# ProProject_ESP32-S3__2023-11-30.net
KiCad netlist of a schematic drawn in EasyEDA Pro
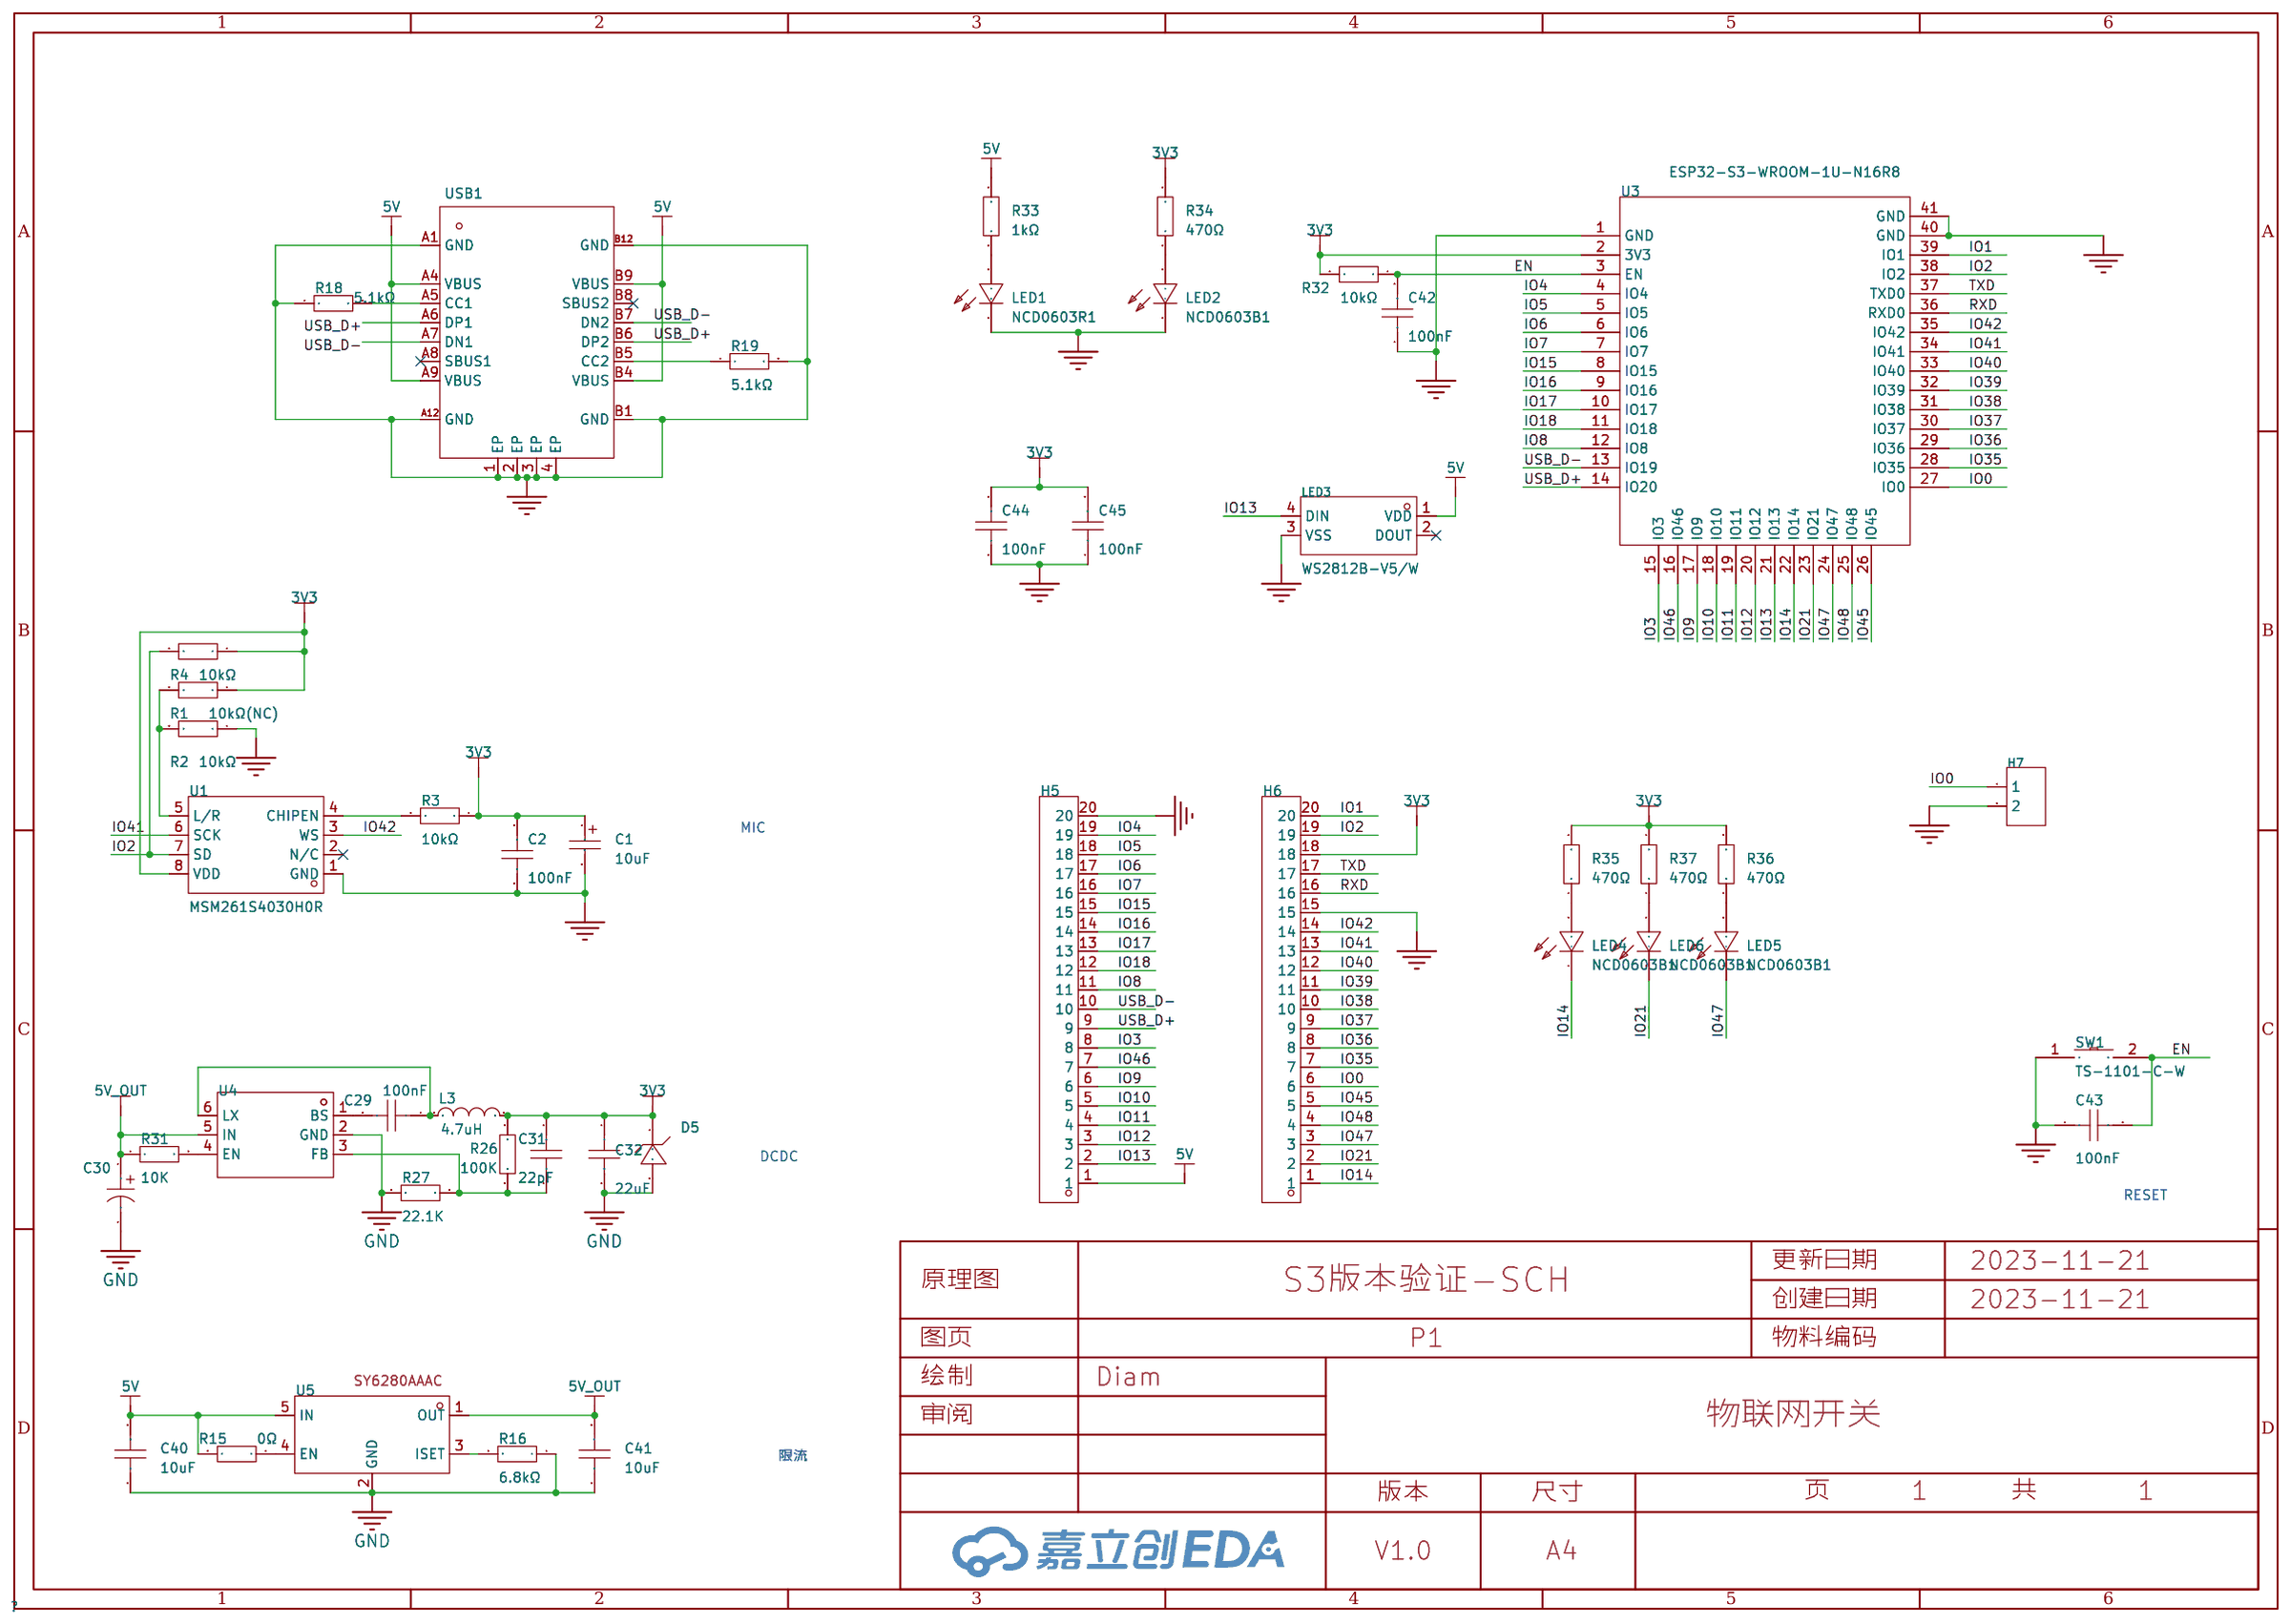
[diagram p0: schematic sheet]

(export (version "E")
  (design (tool "Eeschema 10.0.6"))
  (components
    (comp (ref "C1")
      (value "10uF")
      (footprint "easyedapro:CASE-A_3216")
      (description "容值:10uF;精度:±10%;额定电压:10V;等效串联电阻:3Ω@100kHz;")
      (fields (field (name "Manufacturer Part") "TAJA106K010RNJ") (field (name "Manufacturer") "Kyocera AVX"))
      (libsource (lib "easyedapro") (part "TAJA106K010RNJ"))
    )
    (comp (ref "C2")
      (value "100nF")
      (footprint "easyedapro:C0402")
      (description "容值:100nF;精度:±10%;额定电压:16V;材质(温度系数):X7R;")
      (fields
        (field (name "Manufacturer Part") "GRM155R71C104KA88D")
        (field (name "Manufacturer") "muRata(村田)")
      )
      (libsource (lib "easyedapro") (part "GRM155R71C104KA88D"))
    )
    (comp (ref "C29")
      (value "100nF")
      (footprint "easyedapro:C0603")
      (description "容值:100nF;精度:±10%;额定电压:50V;温度系数:X7R;")
      (libsource (lib "easyedapro") (part "C1210X7R475K630NT"))
    )
    (comp (ref "C30")
      (value "4.7uF")
      (footprint "easyedapro:CAP-SMD_L3.2-W1.6-FD")
      (libsource (lib "easyedapro") (part "YH-475P/T-贴片钽电容"))
    )
    (comp (ref "C31")
      (value "22pF")
      (footprint "easyedapro:C0603")
      (description "容值:100nF;精度:±10%;额定电压:50V;温度系数:X7R;")
      (libsource (lib "easyedapro") (part "C1210X7R475K630NT"))
    )
    (comp (ref "C32")
      (value "22uF")
      (footprint "easyedapro:C0603")
      (description "容值:100nF;精度:±10%;额定电压:50V;温度系数:X7R;")
      (libsource (lib "easyedapro") (part "C1210X7R475K630NT"))
    )
    (comp (ref "C40")
      (value "10uF")
      (footprint "easyedapro:C0603")
      (description "容值:10uF;精度:±20%;额定电压:25V;材质(温度系数):X5R;")
      (fields
        (field (name "Manufacturer Part") "CL10A106MA8NRNC")
        (field (name "Manufacturer") "SAMSUNG(三星)")
      )
      (libsource (lib "easyedapro") (part "CL10A106MA8NRNC"))
    )
    (comp (ref "C41")
      (value "10uF")
      (footprint "easyedapro:C0603")
      (description "容值:10uF;精度:±20%;额定电压:25V;材质(温度系数):X5R;")
      (fields
        (field (name "Manufacturer Part") "CL10A106MA8NRNC")
        (field (name "Manufacturer") "SAMSUNG(三星)")
      )
      (libsource (lib "easyedapro") (part "CL10A106MA8NRNC"))
    )
    (comp (ref "C42")
      (value "100nF")
      (footprint "easyedapro:C0402")
      (description "容值:100nF;精度:±10%;额定电压:16V;材质(温度系数):X7R;")
      (fields
        (field (name "Manufacturer Part") "GRM155R71C104KA88D")
        (field (name "Manufacturer") "muRata(村田)")
      )
      (libsource (lib "easyedapro") (part "GRM155R71C104KA88D"))
    )
    (comp (ref "C43")
      (value "100nF")
      (footprint "easyedapro:C0402")
      (description "容值:100nF;精度:±10%;额定电压:16V;材质(温度系数):X7R;")
      (fields
        (field (name "Manufacturer Part") "GRM155R71C104KA88D")
        (field (name "Manufacturer") "muRata(村田)")
      )
      (libsource (lib "easyedapro") (part "GRM155R71C104KA88D"))
    )
    (comp (ref "C44")
      (value "100nF")
      (footprint "easyedapro:C0402")
      (description "容值:100nF;精度:±10%;额定电压:16V;材质(温度系数):X7R;")
      (fields
        (field (name "Manufacturer Part") "GRM155R71C104KA88D")
        (field (name "Manufacturer") "muRata(村田)")
      )
      (libsource (lib "easyedapro") (part "GRM155R71C104KA88D"))
    )
    (comp (ref "C45")
      (value "100nF")
      (footprint "easyedapro:C0402")
      (description "容值:100nF;精度:±10%;额定电压:16V;材质(温度系数):X7R;")
      (fields
        (field (name "Manufacturer Part") "GRM155R71C104KA88D")
        (field (name "Manufacturer") "muRata(村田)")
      )
      (libsource (lib "easyedapro") (part "GRM155R71C104KA88D"))
    )
    (comp (ref "D5")
      (value "BZT52B3V3")
      (footprint "easyedapro:SOD-123_L2.7-W1.6-LS3.7-RD")
      (description "二极管配置:独立式;稳压值(标称值):3.3V;稳压值(范围):3.23V~3.37V;精度:-;功率:500mW;反向电流(Ir):5A@1V;阻抗(Zzt):95Ω;")
      (fields (field (name "Manufacturer") "AnBon(台湾安邦)"))
      (libsource (lib "easyedapro") (part "BZT52B3V3_C541632"))
    )
    (comp (ref "H5")
      (value "~")
      (footprint "easyedapro:HDR-TH_20P-P2.54-V-M-1")
      (libsource (lib "easyedapro") (part "HDR_2.54-1x20P"))
    )
    (comp (ref "H6")
      (value "~")
      (footprint "easyedapro:HDR-TH_20P-P2.54-V-M-1")
      (libsource (lib "easyedapro") (part "HDR_2.54-1x20P"))
    )
    (comp (ref "H7")
      (value "~")
      (footprint "easyedapro:HDR-TH_2P-P2.54-V-F")
      (libsource (lib "easyedapro") (part "Header-Female-2.54_1x2"))
    )
    (comp (ref "L3")
      (value "4.7uH")
      (footprint "easyedapro:IND-SMD_L4.5-W4.0-1")
      (description "电感值:4.7uH;精度:±20%;额定电流:2.2A;饱和电流(Isat):3.5A;直流电阻(DCR):98mΩ;")
      (fields (field (name "Manufacturer Part") "MCS0420-4R7MPN2") (field (name "Manufacturer") "PSA(信昌电陶)"))
      (libsource (lib "easyedapro") (part "MCS0420-4R7MPN2"))
    )
    (comp (ref "LED1")
      (value "NCD0603R1")
      (footprint "easyedapro:LED0603-RD_RED")
      (description "发光颜色:红色;功率:65mW;透镜颜色:无色透明;主波长:615nm~630nm;发光强度:80mcd~220mcd;发光角度:130°;工作温度:-30°C~+85°C;")
      (fields (field (name "Manufacturer") "国星光电"))
      (libsource (lib "easyedapro") (part "FC-DA1608HRK-620D"))
    )
    (comp (ref "LED2")
      (value "NCD0603B1")
      (footprint "easyedapro:LED0603-RD")
      (description "发光颜色:蓝色;功率:72mW;透镜颜色:无色透明;主波长:463nm~475nm;发光强度:80mcd~220mcd;发光角度:130°;工作温度:-30°C~+85°C;")
      (fields (field (name "Manufacturer") "国星光电"))
      (libsource (lib "easyedapro") (part "FC-DA1608BK-470H10"))
    )
    (comp (ref "LED3")
      (value "WS2812B-V5/W")
      (footprint "easyedapro:LED-SMD_4P-L5.0-W5.0-TL-1")
      (description "无需外围元器件，有反接保护和过压保护，游乐设备，消费类电子，电竞领域，电脑周边及设备")
      (fields (field (name "Manufacturer") "worldsemi"))
      (libsource (lib "easyedapro") (part "WS2812B-V5/W"))
    )
    (comp (ref "LED4")
      (value "NCD0603B1")
      (footprint "easyedapro:LED0603-RD")
      (description "发光颜色:蓝色;功率:72mW;透镜颜色:无色透明;主波长:463nm~475nm;发光强度:80mcd~220mcd;发光角度:130°;工作温度:-30°C~+85°C;")
      (fields (field (name "Manufacturer") "国星光电"))
      (libsource (lib "easyedapro") (part "FC-DA1608BK-470H10"))
    )
    (comp (ref "LED5")
      (value "NCD0603B1")
      (footprint "easyedapro:LED0603-RD")
      (description "发光颜色:蓝色;功率:72mW;透镜颜色:无色透明;主波长:463nm~475nm;发光强度:80mcd~220mcd;发光角度:130°;工作温度:-30°C~+85°C;")
      (fields (field (name "Manufacturer") "国星光电"))
      (libsource (lib "easyedapro") (part "FC-DA1608BK-470H10"))
    )
    (comp (ref "LED6")
      (value "NCD0603B1")
      (footprint "easyedapro:LED0603-RD")
      (description "发光颜色:蓝色;功率:72mW;透镜颜色:无色透明;主波长:463nm~475nm;发光强度:80mcd~220mcd;发光角度:130°;工作温度:-30°C~+85°C;")
      (fields (field (name "Manufacturer") "国星光电"))
      (libsource (lib "easyedapro") (part "FC-DA1608BK-470H10"))
    )
    (comp (ref "R1")
      (value "10kΩ(NC)")
      (footprint "easyedapro:R0402")
      (description "电阻类型:厚膜电阻;阻值:10kΩ;精度:±1%;功率:62.5mW;")
      (fields (field (name "Manufacturer Part") "RC0402FR-0710KL") (field (name "Manufacturer") "YAGEO(国巨)"))
      (libsource (lib "easyedapro") (part "RC0402FR-0710KL"))
    )
    (comp (ref "R2")
      (value "10kΩ")
      (footprint "easyedapro:R0402")
      (description "电阻类型:厚膜电阻;阻值:10kΩ;精度:±1%;功率:62.5mW;")
      (fields (field (name "Manufacturer Part") "RC0402FR-0710KL") (field (name "Manufacturer") "YAGEO(国巨)"))
      (libsource (lib "easyedapro") (part "RC0402FR-0710KL"))
    )
    (comp (ref "R3")
      (value "10kΩ")
      (footprint "easyedapro:R0402")
      (description "电阻类型:厚膜电阻;阻值:10kΩ;精度:±1%;功率:62.5mW;")
      (fields (field (name "Manufacturer Part") "RC0402FR-0710KL") (field (name "Manufacturer") "YAGEO(国巨)"))
      (libsource (lib "easyedapro") (part "RC0402FR-0710KL"))
    )
    (comp (ref "R4")
      (value "10kΩ")
      (footprint "easyedapro:R0402")
      (description "电阻类型:厚膜电阻;阻值:10kΩ;精度:±1%;功率:62.5mW;")
      (fields (field (name "Manufacturer Part") "RC0402FR-0710KL") (field (name "Manufacturer") "YAGEO(国巨)"))
      (libsource (lib "easyedapro") (part "RC0402FR-0710KL"))
    )
    (comp (ref "R15")
      (value "0Ω")
      (footprint "easyedapro:R0402")
      (description "电阻类型:厚膜电阻;阻值:0Ω;精度:±5%;功率:62.5mW;")
      (fields
        (field (name "Manufacturer Part") "0402WGJ0000TCE")
        (field (name "Manufacturer") "UNI-ROYAL(厚声)")
      )
      (libsource (lib "easyedapro") (part "0402WGJ0000TCE"))
    )
    (comp (ref "R16")
      (value "6.8kΩ")
      (footprint "easyedapro:R0603")
      (description "电阻类型:厚膜电阻;阻值:6.8kΩ;精度:±1%;功率:100mW;")
      (fields
        (field (name "Manufacturer Part") "0603WAF6801T5E")
        (field (name "Manufacturer") "UNI-ROYAL(厚声)")
      )
      (libsource (lib "easyedapro") (part "0603WAF6801T5E"))
    )
    (comp (ref "R18")
      (value "5.1kΩ")
      (footprint "easyedapro:R0402")
      (description "电阻类型:厚膜电阻;阻值:5.1kΩ;精度:±1%;功率:62.5mW;")
      (fields
        (field (name "Manufacturer Part") "0402WGF5101TCE")
        (field (name "Manufacturer") "UNI-ROYAL(厚声)")
      )
      (libsource (lib "easyedapro") (part "0402WGF5101TCE"))
    )
    (comp (ref "R19")
      (value "5.1kΩ")
      (footprint "easyedapro:R0402")
      (description "电阻类型:厚膜电阻;阻值:5.1kΩ;精度:±1%;功率:62.5mW;")
      (fields
        (field (name "Manufacturer Part") "0402WGF5101TCE")
        (field (name "Manufacturer") "UNI-ROYAL(厚声)")
      )
      (libsource (lib "easyedapro") (part "0402WGF5101TCE"))
    )
    (comp (ref "R26")
      (value "100K")
      (footprint "easyedapro:R0603")
      (libsource (lib "easyedapro") (part "电阻"))
    )
    (comp (ref "R27")
      (value "22.1K")
      (footprint "easyedapro:R0603")
      (libsource (lib "easyedapro") (part "电阻"))
    )
    (comp (ref "R31") (value "10K") (footprint "easyedapro:R0603") (libsource (lib "easyedapro") (part "电阻")))
    (comp (ref "R32")
      (value "10kΩ")
      (footprint "easyedapro:R0402")
      (description "电阻类型:厚膜电阻;阻值:10kΩ;精度:±1%;功率:62.5mW;")
      (fields (field (name "Manufacturer Part") "RC0402FR-0710KL") (field (name "Manufacturer") "YAGEO(国巨)"))
      (libsource (lib "easyedapro") (part "RC0402FR-0710KL"))
    )
    (comp (ref "R33")
      (value "1kΩ")
      (footprint "easyedapro:R0603")
      (description "电阻类型:厚膜电阻;阻值:1kΩ;精度:±1%;功率:100mW;温度系数:±100ppm/°C;")
      (fields
        (field (name "Manufacturer Part") "0603WAF1001T5E")
        (field (name "Manufacturer") "UNI-ROYAL(厚声)")
      )
      (libsource (lib "easyedapro") (part "0603WAF1001T5E"))
    )
    (comp (ref "R34")
      (value "470Ω")
      (footprint "easyedapro:R0603")
      (description "电阻类型:厚膜电阻;阻值:470Ω;精度:±1%;功率:100mW;温度系数:±100ppm/°C;")
      (fields
        (field (name "Manufacturer Part") "0603WAF4700T5E")
        (field (name "Manufacturer") "UNI-ROYAL(厚声)")
      )
      (libsource (lib "easyedapro") (part "0603WAF4700T5E"))
    )
    (comp (ref "R35")
      (value "470Ω")
      (footprint "easyedapro:R0603")
      (description "电阻类型:厚膜电阻;阻值:470Ω;精度:±1%;功率:100mW;温度系数:±100ppm/°C;")
      (fields
        (field (name "Manufacturer Part") "0603WAF4700T5E")
        (field (name "Manufacturer") "UNI-ROYAL(厚声)")
      )
      (libsource (lib "easyedapro") (part "0603WAF4700T5E"))
    )
    (comp (ref "R36")
      (value "470Ω")
      (footprint "easyedapro:R0603")
      (description "电阻类型:厚膜电阻;阻值:470Ω;精度:±1%;功率:100mW;温度系数:±100ppm/°C;")
      (fields
        (field (name "Manufacturer Part") "0603WAF4700T5E")
        (field (name "Manufacturer") "UNI-ROYAL(厚声)")
      )
      (libsource (lib "easyedapro") (part "0603WAF4700T5E"))
    )
    (comp (ref "R37")
      (value "470Ω")
      (footprint "easyedapro:R0603")
      (description "电阻类型:厚膜电阻;阻值:470Ω;精度:±1%;功率:100mW;温度系数:±100ppm/°C;")
      (fields
        (field (name "Manufacturer Part") "0603WAF4700T5E")
        (field (name "Manufacturer") "UNI-ROYAL(厚声)")
      )
      (libsource (lib "easyedapro") (part "0603WAF4700T5E"))
    )
    (comp (ref "SW1")
      (value "TS-1101-C-W")
      (footprint "easyedapro:SW-SMD_L6.0-W3.3-LS8.0")
      (description "电路结构:单刀单掷;带支架:否;触点电流:50mA;额定电压(AC):-;额定电压(DC):12V;额定功率:-;安装方式:立贴;绝缘电阻:-;带灯:无;作用力:260gf;机械寿命:5万次;")
      (fields (field (name "Manufacturer") "XKB Connectivity(中国星坤)"))
      (libsource (lib "easyedapro") (part "TS-1101-C-W"))
    )
    (comp (ref "U1")
      (value "MSM261S4030H0R")
      (footprint "easyedapro:LGA-8_L4.0-W3.0-P1.00-BL")
      (libsource (lib "easyedapro") (part "MSM261S4030H0R"))
    )
    (comp (ref "U3")
      (value "ESP32-S3-WROOM-1U-N16R8")
      (footprint "easyedapro:WIRELM-SMD_ESP32-S3-WROOM-1U")
      (fields (field (name "Manufacturer") "ESPRESSIF(乐鑫)"))
      (libsource (lib "easyedapro") (part "ESP32-S3-WROOM-1U-N16R8"))
    )
    (comp (ref "U4")
      (value "SY8120B1ABC")
      (footprint "easyedapro:SOT-23-6_L2.9-W1.6-P0.95-LS2.8-BR")
      (description "功能类型:降压型;同步整流:-;输出通道数:-;拓扑结构:-;输入电压:-;输出电流(最大值):-;开关频率:-;")
      (fields (field (name "Manufacturer") "矽力杰silergy"))
      (libsource (lib "easyedapro") (part "SY8120B1ABC"))
    )
    (comp (ref "U5")
      (value "SY6280AAAC")
      (footprint "easyedapro:TSOT-23-5_L2.9-W1.6-P0.95-LS2.8-BL")
      (fields (field (name "Manufacturer Part") "SY6280AAAC") (field (name "Manufacturer") "silergy(矽力杰)"))
      (libsource (lib "easyedapro") (part "SY6280AAAC"))
    )
    (comp (ref "USB1")
      (value "~")
      (footprint "easyedapro:USB_TYPE-C-16P")
      (libsource (lib "easyedapro") (part "USB_TYPE-C-16P"))
    )
  )
  (nets
    (net (code "1") (name "/EN") (class "Default")
      (node (ref "C42") (pin "2") (pinfunction "2_2") (pintype "input"))
      (node (ref "C43") (pin "2") (pinfunction "2_2") (pintype "input"))
      (node (ref "R32") (pin "1") (pinfunction "1_1") (pintype "input"))
      (node (ref "SW1") (pin "2") (pinfunction "2_2") (pintype "unspecified"))
      (node (ref "U3") (pin "3") (pinfunction "EN_3") (pintype "unspecified"))
    )
    (net (code "2") (name "/IO0") (class "Default")
      (node (ref "H6") (pin "6") (pinfunction "6_6") (pintype "input"))
      (node (ref "H7") (pin "1") (pinfunction "1_1") (pintype "input"))
      (node (ref "U3") (pin "27") (pinfunction "IO0_27") (pintype "unspecified"))
    )
    (net (code "3") (name "/IO1") (class "Default")
      (node (ref "H6") (pin "20") (pinfunction "20_20") (pintype "input"))
      (node (ref "U3") (pin "39") (pinfunction "IO1_39") (pintype "unspecified"))
    )
    (net (code "4") (name "/IO2") (class "Default")
      (node (ref "H6") (pin "19") (pinfunction "19_19") (pintype "input"))
      (node (ref "R4") (pin "2") (pinfunction "2_2") (pintype "input"))
      (node (ref "U1") (pin "7") (pinfunction "SD_7") (pintype "input"))
      (node (ref "U3") (pin "38") (pinfunction "IO2_38") (pintype "unspecified"))
    )
    (net (code "5") (name "/IO3") (class "Default")
      (node (ref "H5") (pin "8") (pinfunction "8_8") (pintype "input"))
      (node (ref "U3") (pin "15") (pinfunction "IO3_15") (pintype "unspecified"))
    )
    (net (code "6") (name "/IO4") (class "Default")
      (node (ref "H5") (pin "19") (pinfunction "19_19") (pintype "input"))
      (node (ref "U3") (pin "4") (pinfunction "IO4_4") (pintype "unspecified"))
    )
    (net (code "7") (name "/IO5") (class "Default")
      (node (ref "H5") (pin "18") (pinfunction "18_18") (pintype "input"))
      (node (ref "U3") (pin "5") (pinfunction "IO5_5") (pintype "unspecified"))
    )
    (net (code "8") (name "/IO6") (class "Default")
      (node (ref "H5") (pin "17") (pinfunction "17_17") (pintype "input"))
      (node (ref "U3") (pin "6") (pinfunction "IO6_6") (pintype "unspecified"))
    )
    (net (code "9") (name "/IO7") (class "Default")
      (node (ref "H5") (pin "16") (pinfunction "16_16") (pintype "input"))
      (node (ref "U3") (pin "7") (pinfunction "IO7_7") (pintype "unspecified"))
    )
    (net (code "10") (name "/IO8") (class "Default")
      (node (ref "H5") (pin "11") (pinfunction "11_11") (pintype "input"))
      (node (ref "U3") (pin "12") (pinfunction "IO8_12") (pintype "unspecified"))
    )
    (net (code "11") (name "/IO9") (class "Default")
      (node (ref "H5") (pin "6") (pinfunction "6_6") (pintype "input"))
      (node (ref "U3") (pin "17") (pinfunction "IO9_17") (pintype "unspecified"))
    )
    (net (code "12") (name "/IO10") (class "Default")
      (node (ref "H5") (pin "5") (pinfunction "5_5") (pintype "input"))
      (node (ref "U3") (pin "18") (pinfunction "IO10_18") (pintype "unspecified"))
    )
    (net (code "13") (name "/IO11") (class "Default")
      (node (ref "H5") (pin "4") (pinfunction "4_4") (pintype "input"))
      (node (ref "U3") (pin "19") (pinfunction "IO11_19") (pintype "unspecified"))
    )
    (net (code "14") (name "/IO12") (class "Default")
      (node (ref "H5") (pin "3") (pinfunction "3_3") (pintype "input"))
      (node (ref "U3") (pin "20") (pinfunction "IO12_20") (pintype "unspecified"))
    )
    (net (code "15") (name "/IO13") (class "Default")
      (node (ref "H5") (pin "2") (pinfunction "2_2") (pintype "input"))
      (node (ref "LED3") (pin "4") (pinfunction "DIN_4") (pintype "input"))
      (node (ref "U3") (pin "21") (pinfunction "IO13_21") (pintype "unspecified"))
    )
    (net (code "16") (name "/IO14") (class "Default")
      (node (ref "H6") (pin "1") (pinfunction "1_1") (pintype "input"))
      (node (ref "LED4") (pin "1") (pinfunction "-_1") (pintype "input"))
      (node (ref "U3") (pin "22") (pinfunction "IO14_22") (pintype "unspecified"))
    )
    (net (code "17") (name "/IO15") (class "Default")
      (node (ref "H5") (pin "15") (pinfunction "15_15") (pintype "input"))
      (node (ref "U3") (pin "8") (pinfunction "IO15_8") (pintype "unspecified"))
    )
    (net (code "18") (name "/IO16") (class "Default")
      (node (ref "H5") (pin "14") (pinfunction "14_14") (pintype "input"))
      (node (ref "U3") (pin "9") (pinfunction "IO16_9") (pintype "unspecified"))
    )
    (net (code "19") (name "/IO17") (class "Default")
      (node (ref "H5") (pin "13") (pinfunction "13_13") (pintype "input"))
      (node (ref "U3") (pin "10") (pinfunction "IO17_10") (pintype "unspecified"))
    )
    (net (code "20") (name "/IO18") (class "Default")
      (node (ref "H5") (pin "12") (pinfunction "12_12") (pintype "input"))
      (node (ref "U3") (pin "11") (pinfunction "IO18_11") (pintype "unspecified"))
    )
    (net (code "21") (name "/IO21") (class "Default")
      (node (ref "H6") (pin "2") (pinfunction "2_2") (pintype "input"))
      (node (ref "LED6") (pin "1") (pinfunction "-_1") (pintype "input"))
      (node (ref "U3") (pin "23") (pinfunction "IO21_23") (pintype "unspecified"))
    )
    (net (code "22") (name "/IO35") (class "Default")
      (node (ref "H6") (pin "7") (pinfunction "7_7") (pintype "input"))
      (node (ref "U3") (pin "28") (pinfunction "IO35_28") (pintype "unspecified"))
    )
    (net (code "23") (name "/IO36") (class "Default")
      (node (ref "H6") (pin "8") (pinfunction "8_8") (pintype "input"))
      (node (ref "U3") (pin "29") (pinfunction "IO36_29") (pintype "unspecified"))
    )
    (net (code "24") (name "/IO37") (class "Default")
      (node (ref "H6") (pin "9") (pinfunction "9_9") (pintype "input"))
      (node (ref "U3") (pin "30") (pinfunction "IO37_30") (pintype "unspecified"))
    )
    (net (code "25") (name "/IO38") (class "Default")
      (node (ref "H6") (pin "10") (pinfunction "10_10") (pintype "input"))
      (node (ref "U3") (pin "31") (pinfunction "IO38_31") (pintype "unspecified"))
    )
    (net (code "26") (name "/IO39") (class "Default")
      (node (ref "H6") (pin "11") (pinfunction "11_11") (pintype "input"))
      (node (ref "U3") (pin "32") (pinfunction "IO39_32") (pintype "unspecified"))
    )
    (net (code "27") (name "/IO40") (class "Default")
      (node (ref "H6") (pin "12") (pinfunction "12_12") (pintype "input"))
      (node (ref "U3") (pin "33") (pinfunction "IO40_33") (pintype "unspecified"))
    )
    (net (code "28") (name "/IO41") (class "Default")
      (node (ref "H6") (pin "13") (pinfunction "13_13") (pintype "input"))
      (node (ref "U1") (pin "6") (pinfunction "SCK_6") (pintype "input"))
      (node (ref "U3") (pin "34") (pinfunction "IO41_34") (pintype "unspecified"))
    )
    (net (code "29") (name "/IO42") (class "Default")
      (node (ref "H6") (pin "14") (pinfunction "14_14") (pintype "input"))
      (node (ref "U1") (pin "3") (pinfunction "WS_3") (pintype "input"))
      (node (ref "U3") (pin "35") (pinfunction "IO42_35") (pintype "unspecified"))
    )
    (net (code "30") (name "/IO45") (class "Default")
      (node (ref "H6") (pin "5") (pinfunction "5_5") (pintype "input"))
      (node (ref "U3") (pin "26") (pinfunction "IO45_26") (pintype "unspecified"))
    )
    (net (code "31") (name "/IO46") (class "Default")
      (node (ref "H5") (pin "7") (pinfunction "7_7") (pintype "input"))
      (node (ref "U3") (pin "16") (pinfunction "IO46_16") (pintype "unspecified"))
    )
    (net (code "32") (name "/IO47") (class "Default")
      (node (ref "H6") (pin "3") (pinfunction "3_3") (pintype "input"))
      (node (ref "LED5") (pin "1") (pinfunction "-_1") (pintype "input"))
      (node (ref "U3") (pin "24") (pinfunction "IO47_24") (pintype "unspecified"))
    )
    (net (code "33") (name "/IO48") (class "Default")
      (node (ref "H6") (pin "4") (pinfunction "4_4") (pintype "input"))
      (node (ref "U3") (pin "25") (pinfunction "IO48_25") (pintype "unspecified"))
    )
    (net (code "34") (name "/RXD") (class "Default")
      (node (ref "H6") (pin "16") (pinfunction "16_16") (pintype "input"))
      (node (ref "U3") (pin "36") (pinfunction "RXD0_36") (pintype "unspecified"))
    )
    (net (code "35") (name "/TXD") (class "Default")
      (node (ref "H6") (pin "17") (pinfunction "17_17") (pintype "input"))
      (node (ref "U3") (pin "37") (pinfunction "TXD0_37") (pintype "unspecified"))
    )
    (net (code "36") (name "/USB_D+") (class "Default")
      (node (ref "H5") (pin "9") (pinfunction "9_9") (pintype "input"))
      (node (ref "U3") (pin "14") (pinfunction "IO20_14") (pintype "unspecified"))
      (node (ref "USB1") (pin "A6") (pinfunction "DP1_A6") (pintype "input"))
      (node (ref "USB1") (pin "B6") (pinfunction "DP2_B6") (pintype "input"))
    )
    (net (code "37") (name "/USB_D-") (class "Default")
      (node (ref "H5") (pin "10") (pinfunction "10_10") (pintype "input"))
      (node (ref "U3") (pin "13") (pinfunction "IO19_13") (pintype "unspecified"))
      (node (ref "USB1") (pin "A7") (pinfunction "DN1_A7") (pintype "input"))
      (node (ref "USB1") (pin "B7") (pinfunction "DN2_B7") (pintype "input"))
    )
    (net (code "38") (name "3V3") (class "Default")
      (node (ref "C1") (pin "1") (pinfunction "1_1") (pintype "input"))
      (node (ref "C2") (pin "2") (pinfunction "2_2") (pintype "input"))
      (node (ref "C31") (pin "2") (pinfunction "2_2") (pintype "input"))
      (node (ref "C32") (pin "1") (pinfunction "1_1") (pintype "input"))
      (node (ref "C44") (pin "2") (pinfunction "2_2") (pintype "input"))
      (node (ref "C45") (pin "2") (pinfunction "2_2") (pintype "input"))
      (node (ref "D5") (pin "1") (pinfunction "C_1") (pintype "input"))
      (node (ref "H6") (pin "18") (pinfunction "18_18") (pintype "input"))
      (node (ref "L3") (pin "2") (pinfunction "2_2") (pintype "input"))
      (node (ref "R1") (pin "1") (pinfunction "1_1") (pintype "input"))
      (node (ref "R26") (pin "2") (pinfunction "2_2") (pintype "input"))
      (node (ref "R3") (pin "1") (pinfunction "1_1") (pintype "input"))
      (node (ref "R32") (pin "2") (pinfunction "2_2") (pintype "input"))
      (node (ref "R34") (pin "1") (pinfunction "1_1") (pintype "input"))
      (node (ref "R35") (pin "2") (pinfunction "2_2") (pintype "input"))
      (node (ref "R36") (pin "2") (pinfunction "2_2") (pintype "input"))
      (node (ref "R37") (pin "2") (pinfunction "2_2") (pintype "input"))
      (node (ref "R4") (pin "1") (pinfunction "1_1") (pintype "input"))
      (node (ref "U1") (pin "8") (pinfunction "VDD_8") (pintype "input"))
      (node (ref "U3") (pin "2") (pinfunction "3V3_2") (pintype "unspecified"))
    )
    (net (code "39") (name "5V") (class "Default")
      (node (ref "C40") (pin "2") (pinfunction "2_2") (pintype "input"))
      (node (ref "H5") (pin "1") (pinfunction "1_1") (pintype "input"))
      (node (ref "LED3") (pin "1") (pinfunction "VDD_1") (pintype "input"))
      (node (ref "R15") (pin "2") (pinfunction "2_2") (pintype "input"))
      (node (ref "R33") (pin "1") (pinfunction "1_1") (pintype "input"))
      (node (ref "U5") (pin "5") (pinfunction "IN_5") (pintype "input"))
      (node (ref "USB1") (pin "A4") (pinfunction "VBUS_A4") (pintype "input"))
      (node (ref "USB1") (pin "A9") (pinfunction "VBUS_A9") (pintype "input"))
      (node (ref "USB1") (pin "B4") (pinfunction "VBUS_B4") (pintype "input"))
      (node (ref "USB1") (pin "B9") (pinfunction "VBUS_B9") (pintype "input"))
    )
    (net (code "40") (name "5V_OUT") (class "Default")
      (node (ref "C30") (pin "1") (pinfunction "1_1") (pintype "input"))
      (node (ref "C41") (pin "2") (pinfunction "2_2") (pintype "input"))
      (node (ref "R31") (pin "1") (pinfunction "1_1") (pintype "input"))
      (node (ref "U4") (pin "5") (pinfunction "IN_5") (pintype "input"))
      (node (ref "U5") (pin "1") (pinfunction "OUT_1") (pintype "input"))
    )
    (net (code "41") (name "GND") (class "Default")
      (node (ref "C1") (pin "2") (pinfunction "2_2") (pintype "input"))
      (node (ref "C2") (pin "1") (pinfunction "1_1") (pintype "input"))
      (node (ref "C30") (pin "2") (pinfunction "2_2") (pintype "input"))
      (node (ref "C32") (pin "2") (pinfunction "2_2") (pintype "input"))
      (node (ref "C40") (pin "1") (pinfunction "1_1") (pintype "input"))
      (node (ref "C41") (pin "1") (pinfunction "1_1") (pintype "input"))
      (node (ref "C42") (pin "1") (pinfunction "1_1") (pintype "input"))
      (node (ref "C43") (pin "1") (pinfunction "1_1") (pintype "input"))
      (node (ref "C44") (pin "1") (pinfunction "1_1") (pintype "input"))
      (node (ref "C45") (pin "1") (pinfunction "1_1") (pintype "input"))
      (node (ref "D5") (pin "2") (pinfunction "A_2") (pintype "input"))
      (node (ref "H5") (pin "20") (pinfunction "20_20") (pintype "input"))
      (node (ref "H6") (pin "15") (pinfunction "15_15") (pintype "input"))
      (node (ref "H7") (pin "2") (pinfunction "2_2") (pintype "input"))
      (node (ref "LED1") (pin "1") (pinfunction "K_1") (pintype "input"))
      (node (ref "LED2") (pin "1") (pinfunction "-_1") (pintype "input"))
      (node (ref "LED3") (pin "3") (pinfunction "VSS_3") (pintype "input"))
      (node (ref "R16") (pin "1") (pinfunction "1_1") (pintype "input"))
      (node (ref "R18") (pin "1") (pinfunction "1_1") (pintype "input"))
      (node (ref "R19") (pin "2") (pinfunction "2_2") (pintype "input"))
      (node (ref "R2") (pin "1") (pinfunction "1_1") (pintype "input"))
      (node (ref "R27") (pin "2") (pinfunction "2_2") (pintype "input"))
      (node (ref "SW1") (pin "1") (pinfunction "1_1") (pintype "unspecified"))
      (node (ref "U1") (pin "1") (pinfunction "GND_1") (pintype "input"))
      (node (ref "U3") (pin "1") (pinfunction "GND_1") (pintype "unspecified"))
      (node (ref "U3") (pin "40") (pinfunction "GND_40") (pintype "unspecified"))
      (node (ref "U3") (pin "41") (pinfunction "GND_41") (pintype "unspecified"))
      (node (ref "U4") (pin "2") (pinfunction "GND_2") (pintype "input"))
      (node (ref "U5") (pin "2") (pinfunction "GND_2") (pintype "input"))
      (node (ref "USB1") (pin "1") (pinfunction "EP_1") (pintype "input"))
      (node (ref "USB1") (pin "2") (pinfunction "EP_2") (pintype "input"))
      (node (ref "USB1") (pin "3") (pinfunction "EP_3") (pintype "input"))
      (node (ref "USB1") (pin "4") (pinfunction "EP_4") (pintype "input"))
      (node (ref "USB1") (pin "A1") (pinfunction "GND_A1") (pintype "input"))
      (node (ref "USB1") (pin "A12") (pinfunction "GND_A12") (pintype "input"))
      (node (ref "USB1") (pin "B1") (pinfunction "GND_B1") (pintype "input"))
      (node (ref "USB1") (pin "B12") (pinfunction "GND_B12") (pintype "input"))
    )
    (net (code "42") (name "Net-(LED1-A)") (class "Default")
      (node (ref "LED1") (pin "2") (pinfunction "A_2") (pintype "input"))
      (node (ref "R33") (pin "2") (pinfunction "2_2") (pintype "input"))
    )
    (net (code "43") (name "Net-(LED2-+)") (class "Default")
      (node (ref "LED2") (pin "2") (pinfunction "+_2") (pintype "input"))
      (node (ref "R34") (pin "2") (pinfunction "2_2") (pintype "input"))
    )
    (net (code "44") (name "Net-(LED4-+)") (class "Default")
      (node (ref "LED4") (pin "2") (pinfunction "+_2") (pintype "input"))
      (node (ref "R35") (pin "1") (pinfunction "1_1") (pintype "input"))
    )
    (net (code "45") (name "Net-(LED5-+)") (class "Default")
      (node (ref "LED5") (pin "2") (pinfunction "+_2") (pintype "input"))
      (node (ref "R36") (pin "1") (pinfunction "1_1") (pintype "input"))
    )
    (net (code "46") (name "Net-(LED6-+)") (class "Default")
      (node (ref "LED6") (pin "2") (pinfunction "+_2") (pintype "input"))
      (node (ref "R37") (pin "1") (pinfunction "1_1") (pintype "input"))
    )
    (net (code "47") (name "Net-(U1-CHIPEN)") (class "Default")
      (node (ref "R3") (pin "2") (pinfunction "2_2") (pintype "input"))
      (node (ref "U1") (pin "4") (pinfunction "CHIPEN_4") (pintype "input"))
    )
    (net (code "48") (name "Net-(U1-L{slash}R)") (class "Default")
      (node (ref "R1") (pin "2") (pinfunction "2_2") (pintype "input"))
      (node (ref "R2") (pin "2") (pinfunction "2_2") (pintype "input"))
      (node (ref "U1") (pin "5") (pinfunction "L/R_5") (pintype "input"))
    )
    (net (code "49") (name "Net-(U4-BS)") (class "Default")
      (node (ref "C29") (pin "2") (pinfunction "2_2") (pintype "input"))
      (node (ref "U4") (pin "1") (pinfunction "BS_1") (pintype "input"))
    )
    (net (code "50") (name "Net-(U4-EN)") (class "Default")
      (node (ref "R31") (pin "2") (pinfunction "2_2") (pintype "input"))
      (node (ref "U4") (pin "4") (pinfunction "EN_4") (pintype "input"))
    )
    (net (code "51") (name "Net-(U4-FB)") (class "Default")
      (node (ref "C31") (pin "1") (pinfunction "1_1") (pintype "input"))
      (node (ref "R26") (pin "1") (pinfunction "1_1") (pintype "input"))
      (node (ref "R27") (pin "1") (pinfunction "1_1") (pintype "input"))
      (node (ref "U4") (pin "3") (pinfunction "FB_3") (pintype "input"))
    )
    (net (code "52") (name "Net-(U4-LX)") (class "Default")
      (node (ref "C29") (pin "1") (pinfunction "1_1") (pintype "input"))
      (node (ref "L3") (pin "1") (pinfunction "1_1") (pintype "input"))
      (node (ref "U4") (pin "6") (pinfunction "LX_6") (pintype "input"))
    )
    (net (code "53") (name "Net-(U5-EN)") (class "Default")
      (node (ref "R15") (pin "1") (pinfunction "1_1") (pintype "input"))
      (node (ref "U5") (pin "4") (pinfunction "EN_4") (pintype "input"))
    )
    (net (code "54") (name "Net-(U5-ISET)") (class "Default")
      (node (ref "R16") (pin "2") (pinfunction "2_2") (pintype "input"))
      (node (ref "U5") (pin "3") (pinfunction "ISET_3") (pintype "input"))
    )
    (net (code "55") (name "Net-(USB1-CC1)") (class "Default")
      (node (ref "R18") (pin "2") (pinfunction "2_2") (pintype "input"))
      (node (ref "USB1") (pin "A5") (pinfunction "CC1_A5") (pintype "input"))
    )
    (net (code "56") (name "Net-(USB1-CC2)") (class "Default")
      (node (ref "R19") (pin "1") (pinfunction "1_1") (pintype "input"))
      (node (ref "USB1") (pin "B5") (pinfunction "CC2_B5") (pintype "input"))
    )
    (net (code "57") (name "unconnected-(LED3-DOUT-Pad2)") (class "Default")
      (node (ref "LED3") (pin "2") (pinfunction "DOUT_2") (pintype "input+no_connect"))
    )
    (net (code "58") (name "unconnected-(U1-N{slash}C-Pad2)") (class "Default")
      (node (ref "U1") (pin "2") (pinfunction "N/C_2") (pintype "input+no_connect"))
    )
    (net (code "59") (name "unconnected-(USB1-SBUS1-PadA8)") (class "Default")
      (node (ref "USB1") (pin "A8") (pinfunction "SBUS1_A8") (pintype "input+no_connect"))
    )
    (net (code "60") (name "unconnected-(USB1-SBUS2-PadB8)") (class "Default")
      (node (ref "USB1") (pin "B8") (pinfunction "SBUS2_B8") (pintype "input+no_connect"))
    )
  )
)
